# Enclosure_100x68_SP.net
KiCad netlist of a schematic drawn in EAGLE
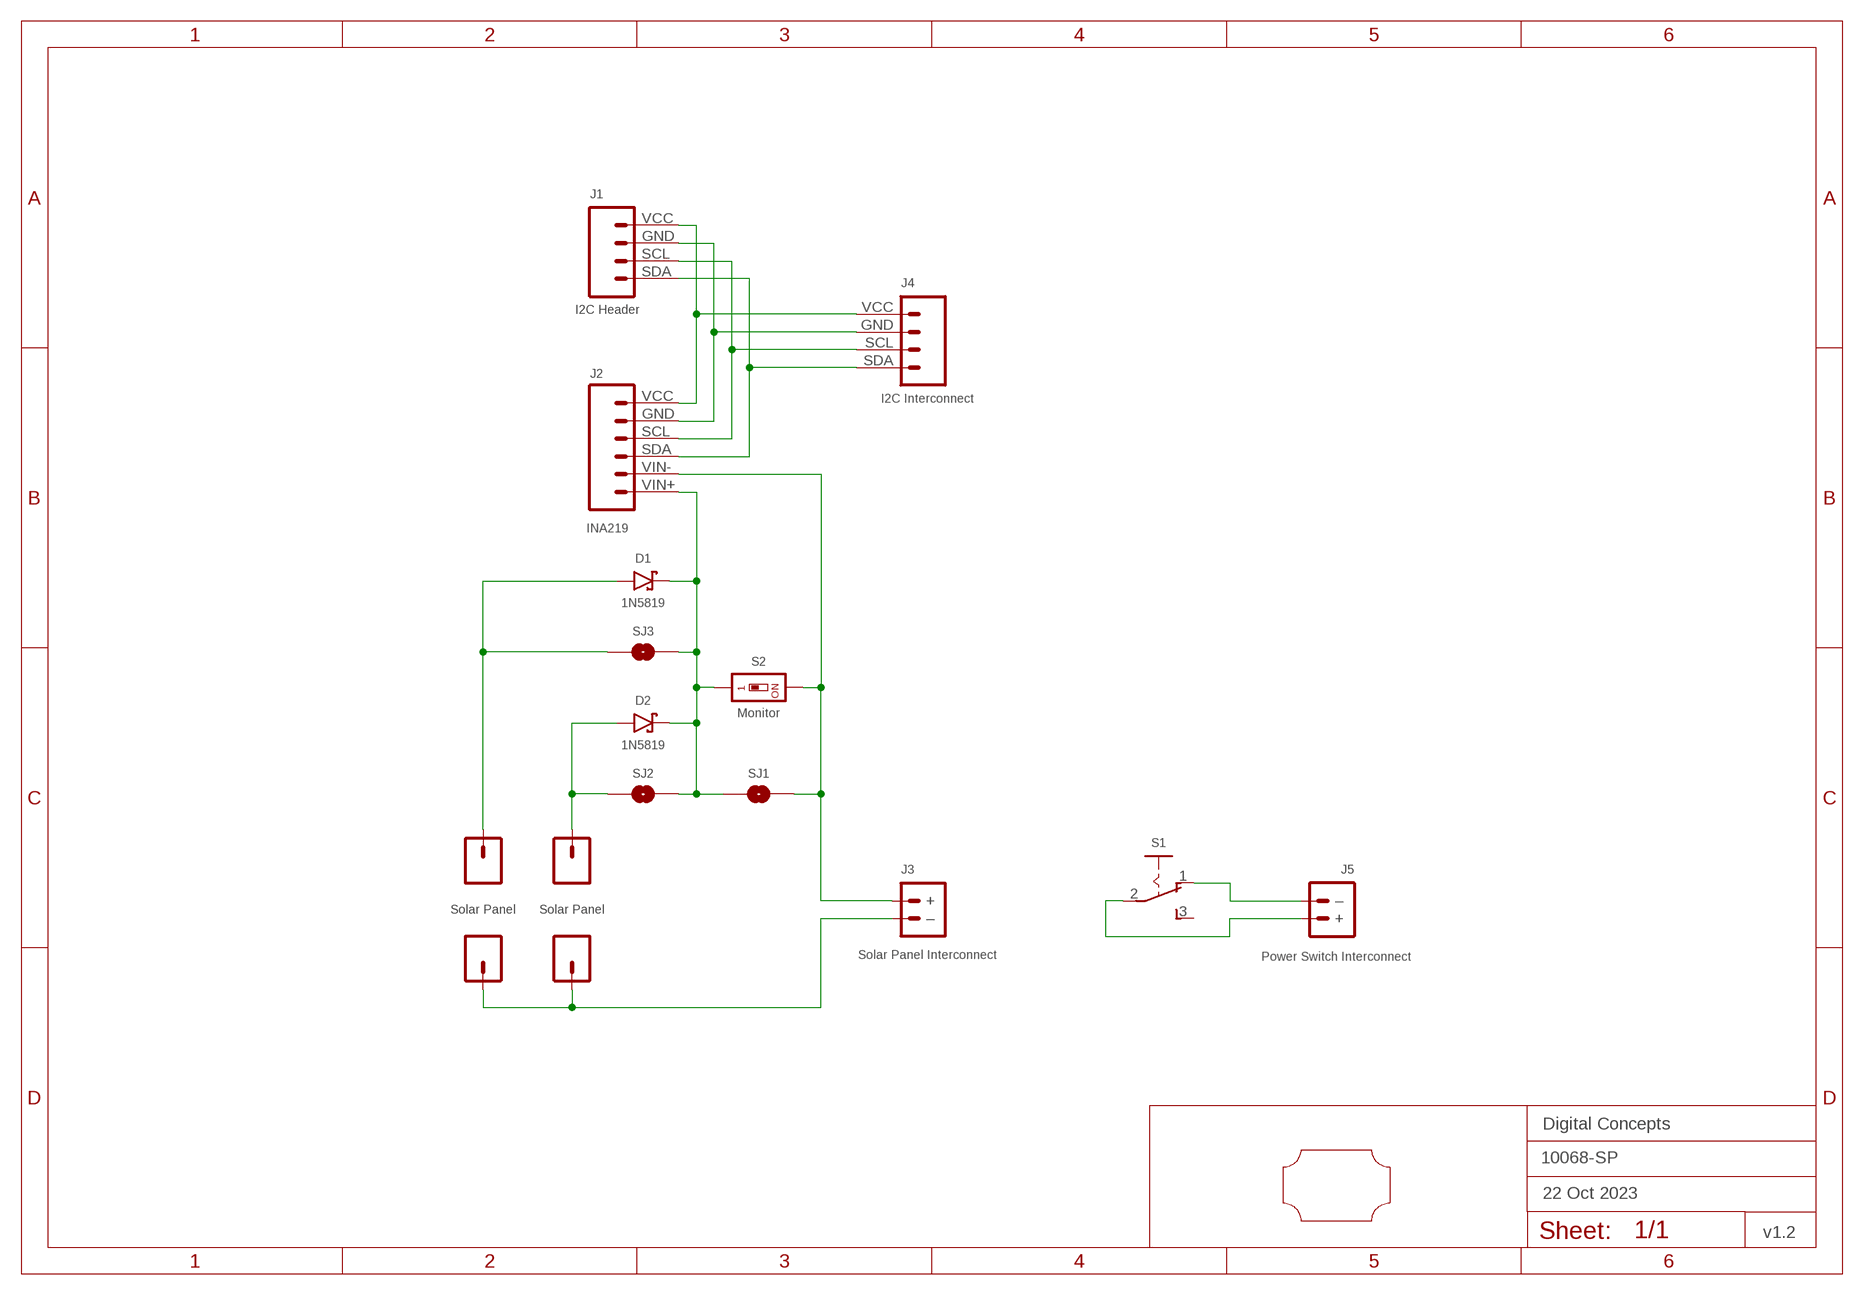
[diagram p0: schematic, sheet 1]

(export (version "E")
  (design (tool "Eeschema 10.0.6"))
  (components
    (comp (ref "+")
      (value "Solar Panel")
      (footprint "eagle-import:PAD-SMD-GENERIC")
      (libsource (lib "eagle-import") (part "PAD-SMD-GENERIC-SQUARE"))
    )
    (comp (ref "+1")
      (value "Solar Panel")
      (footprint "eagle-import:PAD-SMD-GENERIC")
      (libsource (lib "eagle-import") (part "PAD-SMD-GENERIC-SQUARE"))
    )
    (comp (ref "-")
      (value "Solar Panel")
      (footprint "eagle-import:PAD-SMD-GENERIC")
      (libsource (lib "eagle-import") (part "PAD-SMD-GENERIC-SQUARE"))
    )
    (comp (ref "-1")
      (value "Solar Panel")
      (footprint "eagle-import:PAD-SMD-GENERIC")
      (libsource (lib "eagle-import") (part "PAD-SMD-GENERIC-SQUARE"))
    )
    (comp (ref "D1")
      (value "1N5819")
      (footprint "eagle-import:SOD-123")
      (libsource (lib "eagle-import") (part "DIODE-SCHOTTKY-1N5819"))
    )
    (comp (ref "D2")
      (value "1N5819")
      (footprint "eagle-import:SOD-123")
      (libsource (lib "eagle-import") (part "DIODE-SCHOTTKY-1N5819"))
    )
    (comp (ref "J1")
      (value "I2C Header")
      (footprint "eagle-import:CONN_04-I2C")
      (libsource (lib "eagle-import") (part "HEADER-1X4-I2C"))
    )
    (comp (ref "J2")
      (value "INA219")
      (footprint "eagle-import:CONN_06-INA219")
      (libsource (lib "eagle-import") (part "INA219-I2C-MODULE"))
    )
    (comp (ref "J3")
      (value "Solar Panel Interconnect")
      (footprint "eagle-import:JST-PH2.0-2-HORIZONTAL")
      (libsource (lib "eagle-import") (part "JST-PH2.0-2-HORIZONTALJST-PTH-2"))
    )
    (comp (ref "J4")
      (value "I2C Interconnect")
      (footprint "eagle-import:JST-PH2.0-4-HORIZONTAL")
      (libsource (lib "eagle-import") (part "JST-PH2.0-4-I2C-HORIZONTAL"))
    )
    (comp (ref "J5")
      (value "Power Switch Interconnect")
      (footprint "eagle-import:JST-PH2.0-2-HORIZONTAL")
      (libsource (lib "eagle-import") (part "JST-PH2.0-2-HORIZONTALJST-PTH-2"))
    )
    (comp (ref "S1")
      (value "SWITCH-SLIDE-SPDT")
      (footprint "eagle-import:SWITCH-SPDT-PTH")
      (libsource (lib "eagle-import") (part "SWITCH-SLIDE-SPDT"))
    )
    (comp (ref "S2")
      (value "Monitor")
      (footprint "eagle-import:SMD-001")
      (libsource (lib "eagle-import") (part "SWITCH-DIP-SWS001"))
    )
    (comp (ref "SJ1") (value "SJ") (footprint "eagle-import:SJ") (libsource (lib "eagle-import") (part "SJ")))
    (comp (ref "SJ2") (value "SJ") (footprint "eagle-import:SJ") (libsource (lib "eagle-import") (part "SJ")))
    (comp (ref "SJ3") (value "SJ") (footprint "eagle-import:SJ") (libsource (lib "eagle-import") (part "SJ")))
    (comp (ref "U$1")
      (value "PROTO-34X22-SP")
      (footprint "eagle-import:PROTO-34X22-SP")
      (libsource (lib "eagle-import") (part "PROTO-34X22-SP"))
    )
  )
  (nets
    (net (code "1") (name "Net-(+-1)") (class "Default")
      (node (ref "+") (pin "P$1") (pinfunction "1_P$1") (pintype "passive"))
      (node (ref "D2") (pin "A") (pinfunction "A_A") (pintype "passive"))
      (node (ref "SJ2") (pin "1") (pinfunction "1_1") (pintype "passive"))
    )
    (net (code "2") (name "Net-(+1-1)") (class "Default")
      (node (ref "+1") (pin "P$1") (pinfunction "1_P$1") (pintype "passive"))
      (node (ref "D1") (pin "A") (pinfunction "A_A") (pintype "passive"))
      (node (ref "SJ3") (pin "1") (pinfunction "1_1") (pintype "passive"))
    )
    (net (code "3") (name "Net-(--1)") (class "Default")
      (node (ref "-") (pin "P$1") (pinfunction "1_P$1") (pintype "passive"))
      (node (ref "-1") (pin "P$1") (pinfunction "1_P$1") (pintype "passive"))
      (node (ref "J3") (pin "2") (pinfunction "–_2") (pintype "power_in"))
    )
    (net (code "4") (name "Net-(J1-1)") (class "Default")
      (node (ref "J1") (pin "VCC") (pinfunction "1_VCC") (pintype "passive"))
      (node (ref "J2") (pin "VCC") (pinfunction "1_VCC") (pintype "passive"))
      (node (ref "J4") (pin "VCC") (pinfunction "4_VCC") (pintype "passive"))
    )
    (net (code "5") (name "Net-(J1-2)") (class "Default")
      (node (ref "J1") (pin "GND") (pinfunction "2_GND") (pintype "passive"))
      (node (ref "J2") (pin "GND") (pinfunction "2_GND") (pintype "passive"))
      (node (ref "J4") (pin "GND") (pinfunction "3_GND") (pintype "passive"))
    )
    (net (code "6") (name "Net-(J1-3)") (class "Default")
      (node (ref "J1") (pin "SCL") (pinfunction "3_SCL") (pintype "passive"))
      (node (ref "J2") (pin "SCL") (pinfunction "3_SCL") (pintype "passive"))
      (node (ref "J4") (pin "SCL") (pinfunction "2_SCL") (pintype "passive"))
    )
    (net (code "7") (name "Net-(J1-4)") (class "Default")
      (node (ref "J1") (pin "SDA") (pinfunction "4_SDA") (pintype "passive"))
      (node (ref "J2") (pin "SDA") (pinfunction "4_SDA") (pintype "passive"))
      (node (ref "J4") (pin "SDA") (pinfunction "1_SDA") (pintype "passive"))
    )
    (net (code "8") (name "Net-(J2-5)") (class "Default")
      (node (ref "J2") (pin "VIN-") (pinfunction "5_VIN-") (pintype "passive"))
      (node (ref "J3") (pin "1") (pinfunction "+_1") (pintype "power_in"))
      (node (ref "S2") (pin "2") (pinfunction "2_2") (pintype "passive"))
      (node (ref "SJ1") (pin "2") (pinfunction "2_2") (pintype "passive"))
    )
    (net (code "9") (name "Net-(J2-6)") (class "Default")
      (node (ref "D1") (pin "C") (pinfunction "C_C") (pintype "passive"))
      (node (ref "D2") (pin "C") (pinfunction "C_C") (pintype "passive"))
      (node (ref "J2") (pin "VIN+") (pinfunction "6_VIN+") (pintype "passive"))
      (node (ref "S2") (pin "1") (pinfunction "1_1") (pintype "passive"))
      (node (ref "SJ1") (pin "1") (pinfunction "1_1") (pintype "passive"))
      (node (ref "SJ2") (pin "2") (pinfunction "2_2") (pintype "passive"))
      (node (ref "SJ3") (pin "2") (pinfunction "2_2") (pintype "passive"))
    )
    (net (code "10") (name "Net-(J5-+)") (class "Default")
      (node (ref "J5") (pin "1") (pinfunction "+_1") (pintype "power_in"))
      (node (ref "S1") (pin "2") (pinfunction "P_2") (pintype "passive"))
    )
    (net (code "11") (name "Net-(J5-–)") (class "Default")
      (node (ref "J5") (pin "2") (pinfunction "–_2") (pintype "power_in"))
      (node (ref "S1") (pin "1") (pinfunction "O_1") (pintype "passive"))
    )
    (net (code "12") (name "unconnected-(S1-S-Pad3)") (class "Default")
      (node (ref "S1") (pin "3") (pinfunction "S_3") (pintype "passive"))
    )
  )
)
